# MCU.net
KiCad netlist of a schematic drawn in Altium Designer
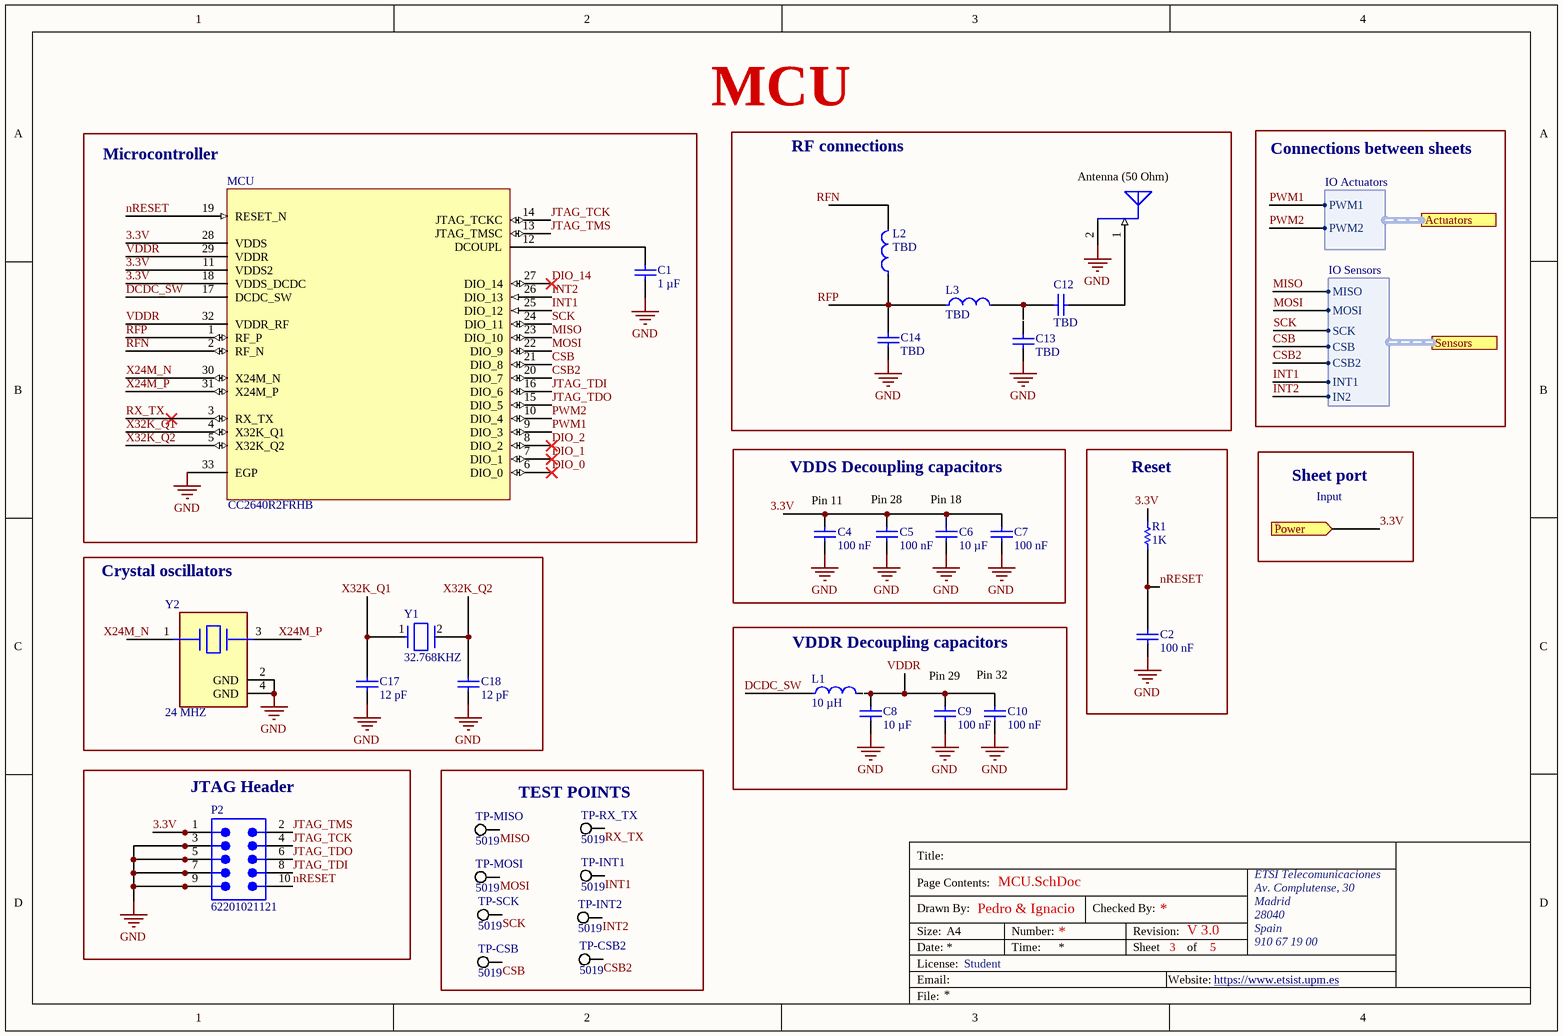
[diagram p0: MCU.SchDoc]

(export (version "E")
  (design (tool "Eeschema 10.0.6"))
  (components
    (comp (ref "Antenna")
      (value "-")
      (footprint "PCBAntenna")
      (libsource (lib "FEEL2324") (part "PCBAntenna"))
    )
    (comp (ref "C1")
      (value "1 µF")
      (footprint "CAPC2013X135X45LL10T25")
      (fields (field (name "MANUFACTURER") "Murata") (field (name "PART NUMBER") "GRM21BR71H105KA12L"))
      (libsource (lib "Altium Content Vault") (part "CAP"))
    )
    (comp (ref "C2")
      (value "100 nF")
      (footprint "CAPC1005X55X30LL05T10")
      (fields (field (name "MANUFACTURER") "Kemet") (field (name "PART NUMBER") "C0402C104K4RACTU"))
      (libsource (lib "Altium Content Vault") (part "CAP"))
    )
    (comp (ref "C4")
      (value "100 nF")
      (footprint "CAPC1005X55X30LL05T10")
      (fields (field (name "MANUFACTURER") "Kemet") (field (name "PART NUMBER") "C0402C104K4RACTU"))
      (libsource (lib "Altium Content Vault") (part "CAP"))
    )
    (comp (ref "C5")
      (value "100 nF")
      (footprint "CAPC1005X55X30LL05T10")
      (fields (field (name "MANUFACTURER") "Kemet") (field (name "PART NUMBER") "C0402C104K4RACTU"))
      (libsource (lib "Altium Content Vault") (part "CAP"))
    )
    (comp (ref "C6")
      (value "10 µF")
      (footprint "MURA-0805_H_1.35_M")
      (description "CAP, Ceramic, 10 uF, 10%, 10 V, 0805, RoHS, Tape and Reel")
      (fields (field (name "MANUFACTURER") "Murata") (field (name "TOLERANCE") "±10%"))
      (libsource (lib "Altium Content Vault") (part "CAP-NP-2"))
    )
    (comp (ref "C7")
      (value "100 nF")
      (footprint "CAPC1005X55X30LL05T10")
      (fields (field (name "MANUFACTURER") "Kemet") (field (name "PART NUMBER") "C0402C104K4RACTU"))
      (libsource (lib "Altium Content Vault") (part "CAP"))
    )
    (comp (ref "C8")
      (value "10 µF")
      (footprint "MURA-0805_H_1.35_M")
      (description "CAP, Ceramic, 10 uF, 10%, 10 V, 0805, RoHS, Tape and Reel")
      (fields (field (name "MANUFACTURER") "Murata") (field (name "TOLERANCE") "±10%"))
      (libsource (lib "Altium Content Vault") (part "CAP-NP-2"))
    )
    (comp (ref "C9")
      (value "100 nF")
      (footprint "CAPC1005X55X30LL05T10")
      (fields (field (name "MANUFACTURER") "Kemet") (field (name "PART NUMBER") "C0402C104K4RACTU"))
      (libsource (lib "Altium Content Vault") (part "CAP"))
    )
    (comp (ref "C10")
      (value "100 nF")
      (footprint "CAPC1005X55X30LL05T10")
      (fields (field (name "MANUFACTURER") "Kemet") (field (name "PART NUMBER") "C0402C104K4RACTU"))
      (libsource (lib "Altium Content Vault") (part "CAP"))
    )
    (comp (ref "C12")
      (value "TBD")
      (footprint "CAPC2013X135X45LL10T25")
      (fields (field (name "MANUFACTURER") "Murata") (field (name "PART NUMBER") "GRM21BR71H105KA12L"))
      (libsource (lib "Altium Content Vault") (part "CAP"))
    )
    (comp (ref "C13")
      (value "TBD")
      (footprint "CAPC2013X135X45LL10T25")
      (fields (field (name "MANUFACTURER") "Murata") (field (name "PART NUMBER") "GRM21BR71H105KA12L"))
      (libsource (lib "Altium Content Vault") (part "CAP"))
    )
    (comp (ref "C14")
      (value "TBD")
      (footprint "CAPC2013X135X45LL10T25")
      (fields (field (name "MANUFACTURER") "Murata") (field (name "PART NUMBER") "GRM21BR71H105KA12L"))
      (libsource (lib "Altium Content Vault") (part "CAP"))
    )
    (comp (ref "C17")
      (value "12 pF")
      (footprint "CAPC1608X73X35LL10T15")
      (fields
        (field (name "PART NUMBER") "06035J120GBSTR")
        (field (name "MANUFACTURER") "AVX Interconnect / Elco")
      )
      (libsource (lib "Altium Content Vault") (part "CAP"))
    )
    (comp (ref "C18")
      (value "12 pF")
      (footprint "CAPC1608X73X35LL10T15")
      (fields
        (field (name "PART NUMBER") "06035J120GBSTR")
        (field (name "MANUFACTURER") "AVX Interconnect / Elco")
      )
      (libsource (lib "Altium Content Vault") (part "CAP"))
    )
    (comp (ref "L1")
      (value "10 µH")
      (footprint "FP-DFE201210U-MFG")
      (description "FIXED IND 2.2UH 1.2A 228 MOHM")
      (libsource (lib "Altium Content Vault") (part "725321dda6339637d4d059423bc1c3c"))
    )
    (comp (ref "L2")
      (value "TBD")
      (footprint "FP-DFE201210U-MFG")
      (description "FIXED IND 2.2UH 1.2A 228 MOHM")
      (libsource (lib "Altium Content Vault") (part "725321dda6339637d4d059423bc1c3c"))
    )
    (comp (ref "L3")
      (value "TBD")
      (footprint "FP-DFE201210U-MFG")
      (description "FIXED IND 2.2UH 1.2A 228 MOHM")
      (libsource (lib "Altium Content Vault") (part "725321dda6339637d4d059423bc1c3c"))
    )
    (comp (ref "MCU")
      (value "CC2640R2FRHB")
      (footprint "CC2640")
      (libsource (lib "FEEL2324") (part "CC2640R2FRHB"))
    )
    (comp (ref "P2")
      (value "62201021121")
      (footprint "62201021121")
      (libsource (lib "Altium Content Vault") (part "Header_Male_2R_10P"))
    )
    (comp (ref "R1")
      (value "1K")
      (footprint "RESC3216X70X50NL05T20")
      (fields (field (name "MANUFACTURER") "Panasonic") (field (name "PART NUMBER") "ERJ-8GEY0R00V"))
      (libsource (lib "Altium Content Vault") (part "RES"))
    )
    (comp (ref "TP-CSB")
      (value "5019")
      (footprint "KSTN-5019_V")
      (description "Test Point, 1 Position SMD, RoHS, Tape and Reel")
      (libsource (lib "Altium Content Vault") (part "TESTPOINT_WHITE"))
    )
    (comp (ref "TP-CSB2")
      (value "5019")
      (footprint "KSTN-5019_V")
      (description "Test Point, 1 Position SMD, RoHS, Tape and Reel")
      (libsource (lib "Altium Content Vault") (part "TESTPOINT_WHITE"))
    )
    (comp (ref "TP-INT1")
      (value "5019")
      (footprint "KSTN-5019_V")
      (description "Test Point, 1 Position SMD, RoHS, Tape and Reel")
      (libsource (lib "Altium Content Vault") (part "TESTPOINT_WHITE"))
    )
    (comp (ref "TP-INT2")
      (value "5019")
      (footprint "KSTN-5019_V")
      (description "Test Point, 1 Position SMD, RoHS, Tape and Reel")
      (libsource (lib "Altium Content Vault") (part "TESTPOINT_WHITE"))
    )
    (comp (ref "TP-MISO")
      (value "5019")
      (footprint "KSTN-5019_V")
      (description "Test Point, 1 Position SMD, RoHS, Tape and Reel")
      (libsource (lib "Altium Content Vault") (part "TESTPOINT_WHITE"))
    )
    (comp (ref "TP-MOSI")
      (value "5019")
      (footprint "KSTN-5019_V")
      (description "Test Point, 1 Position SMD, RoHS, Tape and Reel")
      (libsource (lib "Altium Content Vault") (part "TESTPOINT_WHITE"))
    )
    (comp (ref "TP-RX_TX")
      (value "5019")
      (footprint "KSTN-5019_V")
      (description "Test Point, 1 Position SMD, RoHS, Tape and Reel")
      (libsource (lib "Altium Content Vault") (part "TESTPOINT_WHITE"))
    )
    (comp (ref "TP-SCK")
      (value "5019")
      (footprint "KSTN-5019_V")
      (description "Test Point, 1 Position SMD, RoHS, Tape and Reel")
      (libsource (lib "Altium Content Vault") (part "TESTPOINT_WHITE"))
    )
    (comp (ref "Y1")
      (value "32.768KHZ")
      (footprint "FP-ABS07-MFG")
      (description "Crystal 32.768kHz ±20ppm (Tol) 12.5pF FUND 70kΩ 2-Pin CSMD T/R")
      (fields (field (name "TOLERANCE") "20ppm"))
      (libsource (lib "Altium Content Vault") (part "c23a69dc6c9e2f18f2079038eb95dd1"))
    )
    (comp (ref "Y2")
      (value "24 MHZ")
      (footprint "FP-ABM11-MFG")
      (description "Crystal 24MHz ±20ppm 10pF SMD-4 2mm x 1.6mm")
      (fields (field (name "TOLERANCE") "20ppm"))
      (libsource (lib "Altium Content Vault") (part "b3c1237d77310e73098bcf11eecb25f"))
    )
  )
  (nets
    (net (code "4") (name "/3.3V") (class "Default")
      (node (ref "C4") (pin "2") (pinfunction "2_2") (pintype "passive"))
      (node (ref "C5") (pin "2") (pinfunction "2_2") (pintype "passive"))
      (node (ref "C6") (pin "2") (pinfunction "2_2") (pintype "passive"))
      (node (ref "C7") (pin "2") (pinfunction "2_2") (pintype "passive"))
      (node (ref "MCU") (pin "11") (pinfunction "VDDS2_11") (pintype "passive"))
      (node (ref "MCU") (pin "18") (pinfunction "VDDS_DCDC_18") (pintype "passive"))
      (node (ref "MCU") (pin "28") (pinfunction "VDDS_28") (pintype "passive"))
      (node (ref "P2") (pin "1") (pinfunction "1_1") (pintype "passive"))
      (node (ref "R1") (pin "2") (pinfunction "2_2") (pintype "passive"))
    )
    (net (code "5") (name "/CSB") (class "Default")
      (node (ref "MCU") (pin "21") (pinfunction "DIO_8_21") (pintype "bidirectional"))
      (node (ref "TP-CSB") (pin "1") (pinfunction "1_1") (pintype "passive"))
    )
    (net (code "6") (name "/CSB2") (class "Default")
      (node (ref "MCU") (pin "20") (pinfunction "DIO_7_20") (pintype "bidirectional"))
      (node (ref "TP-CSB2") (pin "1") (pinfunction "1_1") (pintype "passive"))
    )
    (net (code "7") (name "/DCDC_SW") (class "Default")
      (node (ref "L1") (pin "1") (pinfunction "1_1") (pintype "passive"))
      (node (ref "MCU") (pin "17") (pinfunction "DCDC_SW_17") (pintype "power_in"))
    )
    (net (code "8") (name "/DIO_0") (class "Default")
      (node (ref "MCU") (pin "6") (pinfunction "DIO_0_6") (pintype "bidirectional+no_connect"))
    )
    (net (code "9") (name "/DIO_1") (class "Default")
      (node (ref "MCU") (pin "7") (pinfunction "DIO_1_7") (pintype "bidirectional+no_connect"))
    )
    (net (code "10") (name "/DIO_2") (class "Default")
      (node (ref "MCU") (pin "8") (pinfunction "DIO_2_8") (pintype "bidirectional+no_connect"))
    )
    (net (code "11") (name "/DIO_14") (class "Default")
      (node (ref "MCU") (pin "27") (pinfunction "DIO_14_27") (pintype "bidirectional+no_connect"))
    )
    (net (code "12") (name "/INT1") (class "Default")
      (node (ref "MCU") (pin "25") (pinfunction "DIO_12_25") (pintype "input"))
      (node (ref "TP-INT1") (pin "1") (pinfunction "1_1") (pintype "passive"))
    )
    (net (code "13") (name "/INT2") (class "Default")
      (node (ref "MCU") (pin "26") (pinfunction "DIO_13_26") (pintype "input"))
      (node (ref "TP-INT2") (pin "1") (pinfunction "1_1") (pintype "passive"))
    )
    (net (code "14") (name "/JTAG_TCK") (class "Default")
      (node (ref "MCU") (pin "14") (pinfunction "JTAG_TCKC_14") (pintype "bidirectional"))
      (node (ref "P2") (pin "4") (pinfunction "4_4") (pintype "passive"))
    )
    (net (code "15") (name "/JTAG_TDI") (class "Default")
      (node (ref "MCU") (pin "16") (pinfunction "DIO_6_16") (pintype "bidirectional"))
      (node (ref "P2") (pin "8") (pinfunction "8_8") (pintype "passive"))
    )
    (net (code "16") (name "/JTAG_TDO") (class "Default")
      (node (ref "MCU") (pin "15") (pinfunction "DIO_5_15") (pintype "bidirectional"))
      (node (ref "P2") (pin "6") (pinfunction "6_6") (pintype "passive"))
    )
    (net (code "17") (name "/JTAG_TMS") (class "Default")
      (node (ref "MCU") (pin "13") (pinfunction "JTAG_TMSC_13") (pintype "bidirectional"))
      (node (ref "P2") (pin "2") (pinfunction "2_2") (pintype "passive"))
    )
    (net (code "18") (name "/MISO") (class "Default")
      (node (ref "MCU") (pin "23") (pinfunction "DIO_10_23") (pintype "bidirectional"))
      (node (ref "TP-MISO") (pin "1") (pinfunction "1_1") (pintype "passive"))
    )
    (net (code "19") (name "/MOSI") (class "Default")
      (node (ref "MCU") (pin "22") (pinfunction "DIO_9_22") (pintype "bidirectional"))
      (node (ref "TP-MOSI") (pin "1") (pinfunction "1_1") (pintype "passive"))
    )
    (net (code "20") (name "/PWM1") (class "Default")
      (node (ref "MCU") (pin "9") (pinfunction "DIO_3_9") (pintype "bidirectional"))
    )
    (net (code "21") (name "/PWM2") (class "Default")
      (node (ref "MCU") (pin "10") (pinfunction "DIO_4_10") (pintype "bidirectional"))
    )
    (net (code "22") (name "/RFN") (class "Default")
      (node (ref "L2") (pin "2") (pinfunction "2_2") (pintype "passive"))
      (node (ref "MCU") (pin "2") (pinfunction "RF_N_2") (pintype "bidirectional"))
    )
    (net (code "23") (name "/RFP") (class "Default")
      (node (ref "C14") (pin "2") (pinfunction "2_2") (pintype "passive"))
      (node (ref "L2") (pin "1") (pinfunction "1_1") (pintype "passive"))
      (node (ref "L3") (pin "1") (pinfunction "1_1") (pintype "passive"))
      (node (ref "MCU") (pin "1") (pinfunction "RF_P_1") (pintype "bidirectional"))
    )
    (net (code "24") (name "/RX_TX") (class "Default")
      (node (ref "MCU") (pin "3") (pinfunction "RX_TX_3") (pintype "bidirectional"))
      (node (ref "TP-RX_TX") (pin "1") (pinfunction "1_1") (pintype "passive"))
    )
    (net (code "25") (name "/SCK") (class "Default")
      (node (ref "MCU") (pin "24") (pinfunction "DIO_11_24") (pintype "bidirectional"))
      (node (ref "TP-SCK") (pin "1") (pinfunction "1_1") (pintype "passive"))
    )
    (net (code "26") (name "/VDDR") (class "Default")
      (node (ref "C10") (pin "2") (pinfunction "2_2") (pintype "passive"))
      (node (ref "C8") (pin "2") (pinfunction "2_2") (pintype "passive"))
      (node (ref "C9") (pin "2") (pinfunction "2_2") (pintype "passive"))
      (node (ref "MCU") (pin "29") (pinfunction "VDDR_29") (pintype "power_in"))
      (node (ref "MCU") (pin "32") (pinfunction "VDDR_RF_32") (pintype "power_in"))
    )
    (net (code "27") (name "/X24M_N") (class "Default")
      (node (ref "MCU") (pin "30") (pinfunction "X24M_N_30") (pintype "bidirectional"))
      (node (ref "Y2") (pin "1") (pinfunction "1_1") (pintype "passive"))
    )
    (net (code "28") (name "/X24M_P") (class "Default")
      (node (ref "MCU") (pin "31") (pinfunction "X24M_P_31") (pintype "bidirectional"))
      (node (ref "Y2") (pin "3") (pinfunction "3_3") (pintype "passive"))
    )
    (net (code "29") (name "/X32K_Q1") (class "Default")
      (node (ref "C17") (pin "2") (pinfunction "2_2") (pintype "passive"))
      (node (ref "MCU") (pin "4") (pinfunction "X32K_Q1_4") (pintype "bidirectional"))
      (node (ref "Y1") (pin "1") (pinfunction "1_1") (pintype "passive"))
    )
    (net (code "30") (name "/X32K_Q2") (class "Default")
      (node (ref "C18") (pin "2") (pinfunction "2_2") (pintype "passive"))
      (node (ref "MCU") (pin "5") (pinfunction "X32K_Q2_5") (pintype "bidirectional"))
      (node (ref "Y1") (pin "2") (pinfunction "2_2") (pintype "passive"))
    )
    (net (code "31") (name "/nRESET") (class "Default")
      (node (ref "C2") (pin "2") (pinfunction "2_2") (pintype "passive"))
      (node (ref "MCU") (pin "19") (pinfunction "RESET_N_19") (pintype "input"))
      (node (ref "P2") (pin "10") (pinfunction "10_10") (pintype "passive"))
      (node (ref "R1") (pin "1") (pinfunction "1_1") (pintype "passive"))
    )
    (net (code "34") (name "GND") (class "Default")
      (node (ref "Antenna") (pin "2") (pinfunction "GND_2") (pintype "power_in"))
      (node (ref "C1") (pin "1") (pinfunction "1_1") (pintype "passive"))
      (node (ref "C10") (pin "1") (pinfunction "1_1") (pintype "passive"))
      (node (ref "C14") (pin "1") (pinfunction "1_1") (pintype "passive"))
      (node (ref "C17") (pin "1") (pinfunction "1_1") (pintype "passive"))
      (node (ref "C18") (pin "1") (pinfunction "1_1") (pintype "passive"))
      (node (ref "C2") (pin "1") (pinfunction "1_1") (pintype "passive"))
      (node (ref "C4") (pin "1") (pinfunction "1_1") (pintype "passive"))
      (node (ref "C5") (pin "1") (pinfunction "1_1") (pintype "passive"))
      (node (ref "C6") (pin "1") (pinfunction "1_1") (pintype "passive"))
      (node (ref "C7") (pin "1") (pinfunction "1_1") (pintype "passive"))
      (node (ref "C8") (pin "1") (pinfunction "1_1") (pintype "passive"))
      (node (ref "C9") (pin "1") (pinfunction "1_1") (pintype "passive"))
      (node (ref "MCU") (pin "33") (pinfunction "EGP_33") (pintype "power_in"))
      (node (ref "P2") (pin "3") (pinfunction "3_3") (pintype "passive"))
      (node (ref "P2") (pin "5") (pinfunction "5_5") (pintype "passive"))
      (node (ref "P2") (pin "7") (pinfunction "7_7") (pintype "passive"))
      (node (ref "P2") (pin "9") (pinfunction "9_9") (pintype "passive"))
      (node (ref "Y2") (pin "2") (pinfunction "GND_2") (pintype "power_in"))
      (node (ref "Y2") (pin "4") (pinfunction "GND_4") (pintype "power_in"))
    )
    (net (code "35") (name "Net-(Antenna-FeedPoint)") (class "Default")
      (node (ref "Antenna") (pin "1") (pinfunction "FeedPoint_1") (pintype "input"))
      (node (ref "C12") (pin "1") (pinfunction "1_1") (pintype "passive"))
    )
    (net (code "36") (name "Net-(C12-Pad2)") (class "Default")
      (node (ref "C12") (pin "2") (pinfunction "2_2") (pintype "passive"))
      (node (ref "L3") (pin "2") (pinfunction "2_2") (pintype "passive"))
    )
    (net (code "37") (name "Net-(MCU-DCOUPL)") (class "Default")
      (node (ref "C1") (pin "2") (pinfunction "2_2") (pintype "passive"))
      (node (ref "MCU") (pin "12") (pinfunction "DCOUPL_12") (pintype "power_in"))
    )
    (net (code "38") (name "unconnected-(C13-Pad1)") (class "Default")
      (node (ref "C13") (pin "1") (pinfunction "1_1") (pintype "passive"))
    )
    (net (code "39") (name "unconnected-(C13-Pad2)") (class "Default")
      (node (ref "C13") (pin "2") (pinfunction "2_2") (pintype "passive"))
    )
    (net (code "40") (name "unconnected-(L1-Pad2)") (class "Default")
      (node (ref "L1") (pin "2") (pinfunction "2_2") (pintype "passive"))
    )
  )
)
